# AT89S52_3.net
KiCad netlist of a schematic drawn in Altium Designer
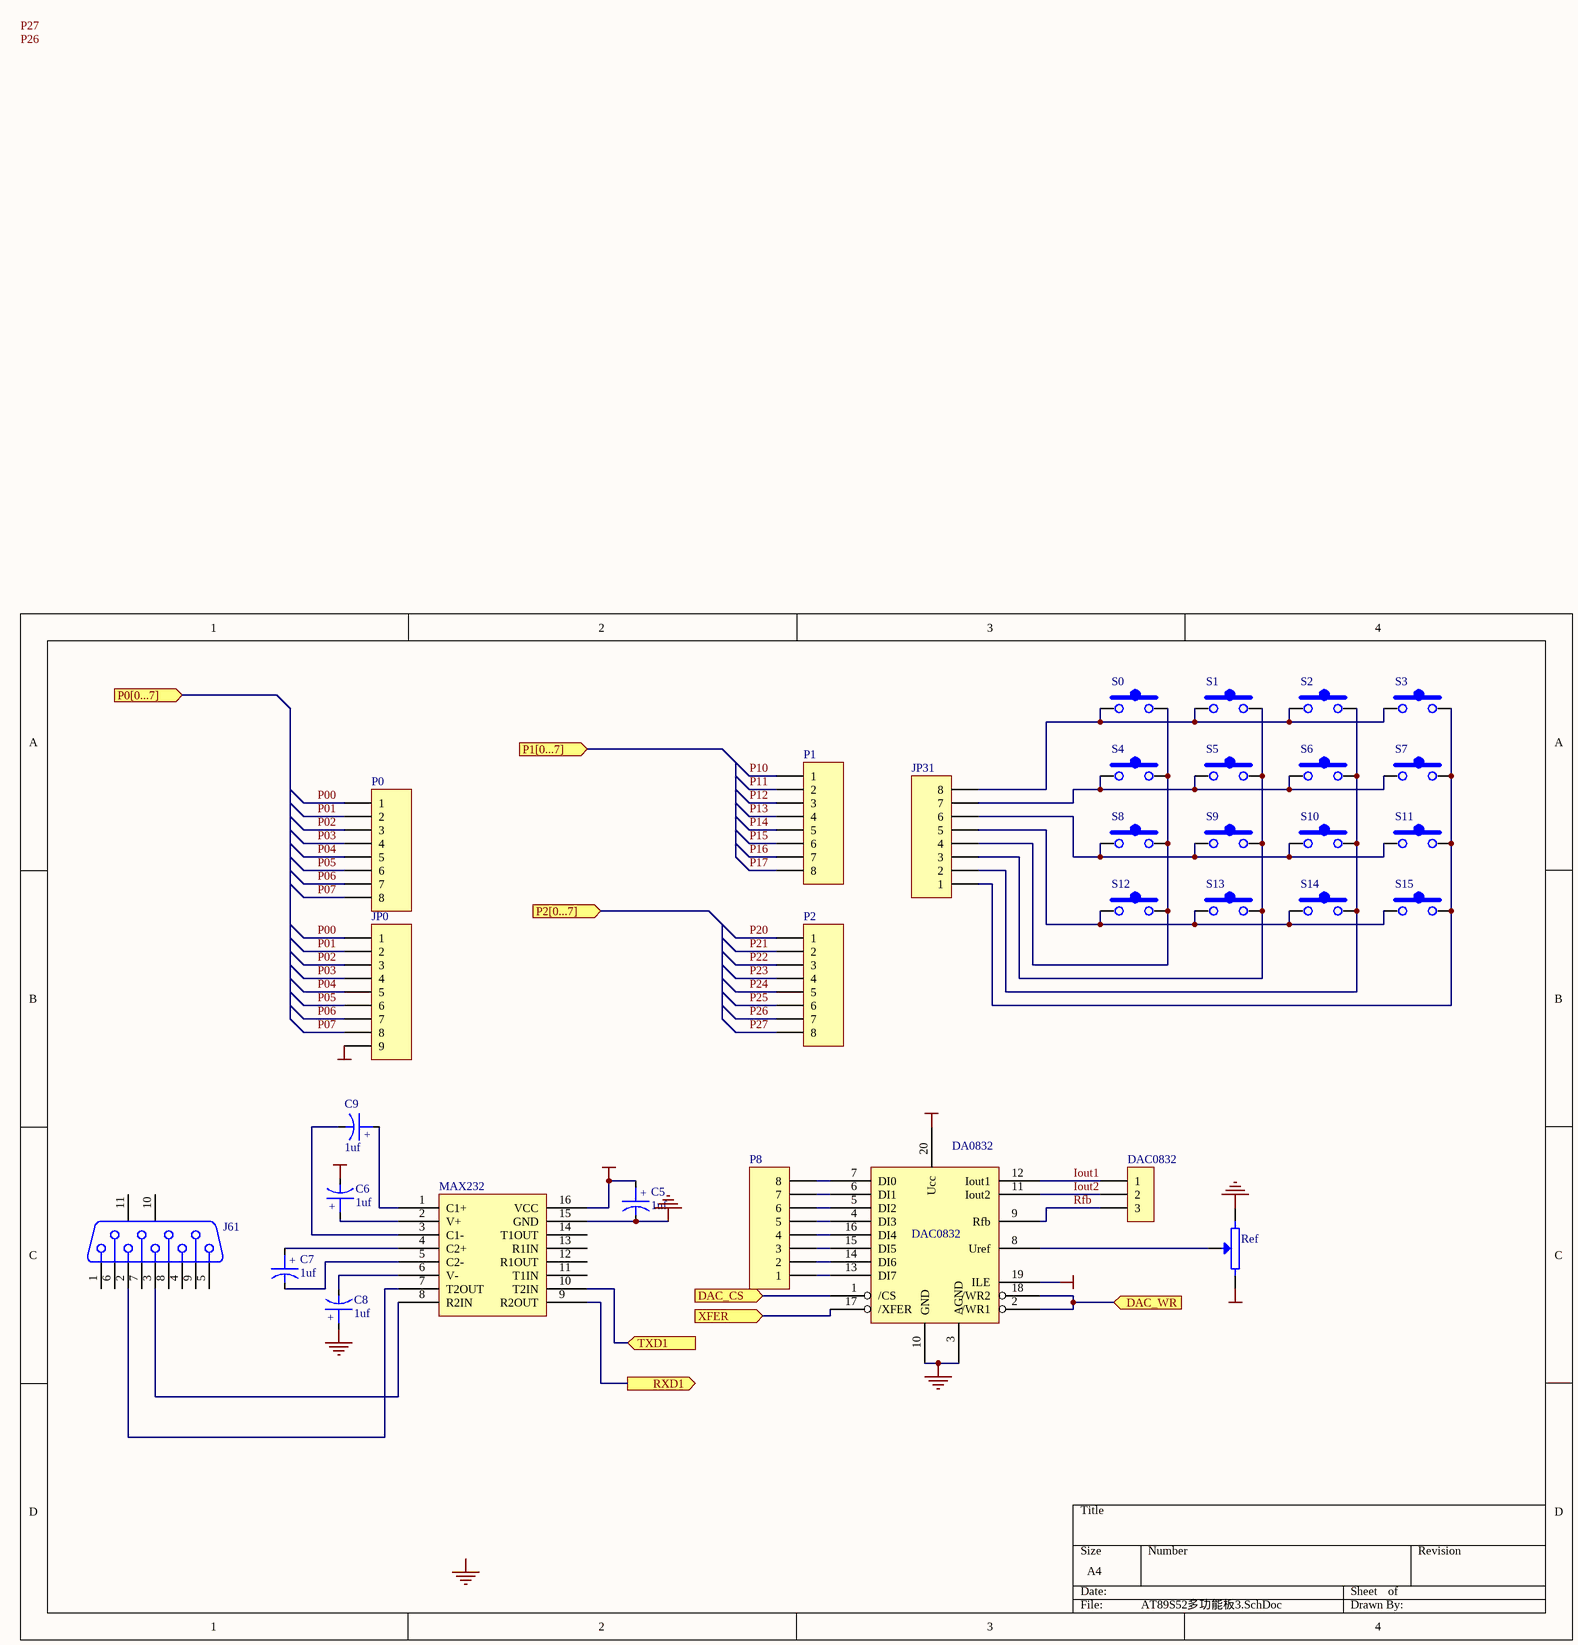
[diagram p0: AT89S52多功能板3.SchDoc]

(export (version "E")
  (design (tool "Eeschema 10.0.6"))
  (components
    (comp (ref "C5")
      (value "1uf")
      (footprint "cap2")
      (description "Capacitor")
      (libsource (lib "*") (part "CAPACITOR POL"))
    )
    (comp (ref "C6")
      (value "1uf")
      (footprint "cap2")
      (description "Capacitor")
      (libsource (lib "*") (part "CAPACITOR POL"))
    )
    (comp (ref "C7")
      (value "1uf")
      (footprint "cap2")
      (description "Capacitor")
      (libsource (lib "*") (part "CAPACITOR POL"))
    )
    (comp (ref "C8")
      (value "1uf")
      (footprint "cap2")
      (description "Capacitor")
      (libsource (lib "*") (part "CAPACITOR POL"))
    )
    (comp (ref "C9")
      (value "1uf")
      (footprint "cap2")
      (description "Capacitor")
      (libsource (lib "*") (part "CAPACITOR POL"))
    )
    (comp (ref "DA0832")
      (value "DA0832")
      (footprint "DAC0832PF")
      (libsource (lib "OldCow1 (1)") (part "DA0832"))
    )
    (comp (ref "DAC0832")
      (value "CON3")
      (footprint "HDR1X3")
      (description "Connector")
      (libsource (lib "OldCow1 (1)") (part "CON3"))
    )
    (comp (ref "J61")
      (value "D Connector 9")
      (footprint "DSUB1.385-2H9")
      (description "Receptacle Assembly, 9 Position, Right Angle")
      (fields (field (name "PUBLISHER") "Altium Limited"))
      (libsource (lib "Miscellaneous Connectors") (part "D Connector 9"))
    )
    (comp (ref "JP0")
      (value "Header 9")
      (footprint "HDR1X9")
      (description "Header, 9-Pin")
      (fields (field (name "PUBLISHER") "Altium Limited"))
      (libsource (lib "Miscellaneous Connectors") (part "Header 9"))
    )
    (comp (ref "JP31")
      (value "Header 8")
      (footprint "HDR1X8")
      (description "Header, 8-Pin")
      (fields (field (name "PUBLISHER") "Altium Limited"))
      (libsource (lib "Miscellaneous Connectors") (part "Header 8"))
    )
    (comp (ref "MAX232") (value "MAX232") (footprint "DIP16") (libsource (lib "*") (part "MAX232")))
    (comp (ref "P0")
      (value "Header 8")
      (footprint "HDR1X8")
      (description "Header, 8-Pin")
      (fields (field (name "PUBLISHER") "Altium Limited"))
      (libsource (lib "") (part "Header 8_1"))
    )
    (comp (ref "P1")
      (value "Header 8")
      (footprint "HDR1X8")
      (description "Header, 8-Pin")
      (fields (field (name "PUBLISHER") "Altium Limited"))
      (libsource (lib "") (part "Header 8_1"))
    )
    (comp (ref "P2")
      (value "Header 8")
      (footprint "HDR1X8")
      (description "Header, 8-Pin")
      (fields (field (name "PUBLISHER") "Altium Limited"))
      (libsource (lib "") (part "Header 8_1"))
    )
    (comp (ref "P8")
      (value "Header 8")
      (footprint "HDR1X8")
      (description "Header, 8-Pin")
      (fields (field (name "PUBLISHER") "Altium Limited"))
      (libsource (lib "Miscellaneous Connectors") (part "Header 8"))
    )
    (comp (ref "Ref")
      (value "25k")
      (footprint "SIP3-D")
      (description "Potentiometer")
      (libsource (lib "OldCow1 (1)") (part "POT2"))
    )
    (comp (ref "S0") (value "KEY") (footprint "KEYPF") (libsource (lib "OldCow1 (1)") (part "KEY")))
    (comp (ref "S1") (value "KEY") (footprint "KEYPF") (libsource (lib "OldCow1 (1)") (part "KEY")))
    (comp (ref "S2") (value "KEY") (footprint "KEYPF") (libsource (lib "OldCow1 (1)") (part "KEY")))
    (comp (ref "S3") (value "KEY") (footprint "KEYPF") (libsource (lib "OldCow1 (1)") (part "KEY")))
    (comp (ref "S4") (value "KEY") (footprint "KEYPF") (libsource (lib "OldCow1 (1)") (part "KEY")))
    (comp (ref "S5") (value "KEY") (footprint "KEYPF") (libsource (lib "OldCow1 (1)") (part "KEY")))
    (comp (ref "S6") (value "KEY") (footprint "KEYPF") (libsource (lib "OldCow1 (1)") (part "KEY")))
    (comp (ref "S7") (value "KEY") (footprint "KEYPF") (libsource (lib "OldCow1 (1)") (part "KEY")))
    (comp (ref "S8") (value "KEY") (footprint "KEYPF") (libsource (lib "OldCow1 (1)") (part "KEY")))
    (comp (ref "S9") (value "KEY") (footprint "KEYPF") (libsource (lib "OldCow1 (1)") (part "KEY")))
    (comp (ref "S10") (value "KEY") (footprint "KEYPF") (libsource (lib "OldCow1 (1)") (part "KEY")))
    (comp (ref "S11") (value "KEY") (footprint "KEYPF") (libsource (lib "OldCow1 (1)") (part "KEY")))
    (comp (ref "S12") (value "KEY") (footprint "KEYPF") (libsource (lib "OldCow1 (1)") (part "KEY")))
    (comp (ref "S13") (value "KEY") (footprint "KEYPF") (libsource (lib "OldCow1 (1)") (part "KEY")))
    (comp (ref "S14") (value "KEY") (footprint "KEYPF") (libsource (lib "OldCow1 (1)") (part "KEY")))
    (comp (ref "S15") (value "KEY") (footprint "KEYPF") (libsource (lib "OldCow1 (1)") (part "KEY")))
  )
  (nets
    (net (code "1") (name "/DAC_CS") (class "Default")
      (node (ref "DA0832") (pin "1") (pinfunction "/CS_1") (pintype "passive"))
    )
    (net (code "2") (name "/DAC_WR") (class "Default")
      (node (ref "DA0832") (pin "18") (pinfunction "/WR2_18") (pintype "passive"))
      (node (ref "DA0832") (pin "2") (pinfunction "/WR1_2") (pintype "passive"))
    )
    (net (code "3") (name "/Iout1") (class "Default")
      (node (ref "DA0832") (pin "12") (pinfunction "Iout1_12") (pintype "passive"))
      (node (ref "DAC0832") (pin "1") (pinfunction "1_1") (pintype "passive"))
    )
    (net (code "4") (name "/Iout2") (class "Default")
      (node (ref "DA0832") (pin "11") (pinfunction "Iout2_11") (pintype "passive"))
      (node (ref "DAC0832") (pin "2") (pinfunction "2_2") (pintype "passive"))
    )
    (net (code "5") (name "/P00") (class "Default")
      (node (ref "JP0") (pin "1") (pinfunction "1_1") (pintype "passive"))
      (node (ref "P0") (pin "1") (pinfunction "1_1") (pintype "passive"))
    )
    (net (code "7") (name "/P01") (class "Default")
      (node (ref "JP0") (pin "2") (pinfunction "2_2") (pintype "passive"))
      (node (ref "P0") (pin "2") (pinfunction "2_2") (pintype "passive"))
    )
    (net (code "9") (name "/P02") (class "Default")
      (node (ref "JP0") (pin "3") (pinfunction "3_3") (pintype "passive"))
      (node (ref "P0") (pin "3") (pinfunction "3_3") (pintype "passive"))
    )
    (net (code "11") (name "/P03") (class "Default")
      (node (ref "JP0") (pin "4") (pinfunction "4_4") (pintype "passive"))
      (node (ref "P0") (pin "4") (pinfunction "4_4") (pintype "passive"))
    )
    (net (code "12") (name "/P04") (class "Default")
      (node (ref "JP0") (pin "5") (pinfunction "5_5") (pintype "passive"))
      (node (ref "P0") (pin "5") (pinfunction "5_5") (pintype "passive"))
    )
    (net (code "13") (name "/P05") (class "Default")
      (node (ref "JP0") (pin "6") (pinfunction "6_6") (pintype "passive"))
      (node (ref "P0") (pin "6") (pinfunction "6_6") (pintype "passive"))
    )
    (net (code "14") (name "/P06") (class "Default")
      (node (ref "JP0") (pin "7") (pinfunction "7_7") (pintype "passive"))
      (node (ref "P0") (pin "7") (pinfunction "7_7") (pintype "passive"))
    )
    (net (code "15") (name "/P07") (class "Default")
      (node (ref "JP0") (pin "8") (pinfunction "8_8") (pintype "passive"))
      (node (ref "P0") (pin "8") (pinfunction "8_8") (pintype "passive"))
    )
    (net (code "16") (name "/P10") (class "Default")
      (node (ref "P1") (pin "1") (pinfunction "1_1") (pintype "passive"))
    )
    (net (code "17") (name "/P11") (class "Default")
      (node (ref "P1") (pin "2") (pinfunction "2_2") (pintype "passive"))
    )
    (net (code "18") (name "/P12") (class "Default")
      (node (ref "P1") (pin "3") (pinfunction "3_3") (pintype "passive"))
    )
    (net (code "19") (name "/P13") (class "Default")
      (node (ref "P1") (pin "4") (pinfunction "4_4") (pintype "passive"))
    )
    (net (code "20") (name "/P14") (class "Default")
      (node (ref "P1") (pin "5") (pinfunction "5_5") (pintype "passive"))
    )
    (net (code "21") (name "/P15") (class "Default")
      (node (ref "P1") (pin "6") (pinfunction "6_6") (pintype "passive"))
    )
    (net (code "22") (name "/P16") (class "Default")
      (node (ref "P1") (pin "7") (pinfunction "7_7") (pintype "passive"))
    )
    (net (code "23") (name "/P17") (class "Default")
      (node (ref "P1") (pin "8") (pinfunction "8_8") (pintype "passive"))
    )
    (net (code "24") (name "/P20") (class "Default")
      (node (ref "P2") (pin "1") (pinfunction "1_1") (pintype "passive"))
    )
    (net (code "25") (name "/P21") (class "Default")
      (node (ref "P2") (pin "2") (pinfunction "2_2") (pintype "passive"))
    )
    (net (code "26") (name "/P22") (class "Default")
      (node (ref "P2") (pin "3") (pinfunction "3_3") (pintype "passive"))
    )
    (net (code "27") (name "/P23") (class "Default")
      (node (ref "P2") (pin "4") (pinfunction "4_4") (pintype "passive"))
    )
    (net (code "28") (name "/P24") (class "Default")
      (node (ref "P2") (pin "5") (pinfunction "5_5") (pintype "passive"))
    )
    (net (code "29") (name "/P25") (class "Default")
      (node (ref "P2") (pin "6") (pinfunction "6_6") (pintype "passive"))
    )
    (net (code "30") (name "/P26") (class "Default")
      (node (ref "P2") (pin "7") (pinfunction "7_7") (pintype "passive"))
    )
    (net (code "31") (name "/P27") (class "Default")
      (node (ref "P2") (pin "8") (pinfunction "8_8") (pintype "passive"))
    )
    (net (code "32") (name "/RXD1") (class "Default")
      (node (ref "MAX232") (pin "9") (pinfunction "R2OUT_9") (pintype "passive"))
    )
    (net (code "33") (name "/Rfb") (class "Default")
      (node (ref "DA0832") (pin "9") (pinfunction "Rfb_9") (pintype "passive"))
      (node (ref "DAC0832") (pin "3") (pinfunction "3_3") (pintype "passive"))
    )
    (net (code "34") (name "/TXD1") (class "Default")
      (node (ref "MAX232") (pin "10") (pinfunction "T2IN_10") (pintype "passive"))
    )
    (net (code "35") (name "/XFER") (class "Default")
      (node (ref "DA0832") (pin "17") (pinfunction "/XFER_17") (pintype "passive"))
    )
    (net (code "36") (name "GND") (class "Default")
      (node (ref "C5") (pin "2") (pinfunction "2_2") (pintype "passive"))
      (node (ref "C8") (pin "1") (pinfunction "1_1") (pintype "passive"))
      (node (ref "DA0832") (pin "10") (pinfunction "GND_10") (pintype "passive"))
      (node (ref "DA0832") (pin "3") (pinfunction "AGND_3") (pintype "passive"))
      (node (ref "MAX232") (pin "15") (pinfunction "GND_15") (pintype "passive"))
      (node (ref "Ref") (pin "2") (pinfunction "2_2") (pintype "passive"))
    )
    (net (code "37") (name "Net-(DA0832-DI0)") (class "Default")
      (node (ref "DA0832") (pin "7") (pinfunction "DI0_7") (pintype "passive"))
      (node (ref "P8") (pin "8") (pinfunction "8_8") (pintype "passive"))
    )
    (net (code "38") (name "Net-(DA0832-DI1)") (class "Default")
      (node (ref "DA0832") (pin "6") (pinfunction "DI1_6") (pintype "passive"))
      (node (ref "P8") (pin "7") (pinfunction "7_7") (pintype "passive"))
    )
    (net (code "39") (name "Net-(DA0832-DI2)") (class "Default")
      (node (ref "DA0832") (pin "5") (pinfunction "DI2_5") (pintype "passive"))
      (node (ref "P8") (pin "6") (pinfunction "6_6") (pintype "passive"))
    )
    (net (code "40") (name "Net-(DA0832-DI3)") (class "Default")
      (node (ref "DA0832") (pin "4") (pinfunction "DI3_4") (pintype "passive"))
      (node (ref "P8") (pin "5") (pinfunction "5_5") (pintype "passive"))
    )
    (net (code "41") (name "Net-(DA0832-DI4)") (class "Default")
      (node (ref "DA0832") (pin "16") (pinfunction "DI4_16") (pintype "passive"))
      (node (ref "P8") (pin "4") (pinfunction "4_4") (pintype "passive"))
    )
    (net (code "42") (name "Net-(DA0832-DI5)") (class "Default")
      (node (ref "DA0832") (pin "15") (pinfunction "DI5_15") (pintype "passive"))
      (node (ref "P8") (pin "3") (pinfunction "3_3") (pintype "passive"))
    )
    (net (code "43") (name "Net-(DA0832-DI6)") (class "Default")
      (node (ref "DA0832") (pin "14") (pinfunction "DI6_14") (pintype "passive"))
      (node (ref "P8") (pin "2") (pinfunction "2_2") (pintype "passive"))
    )
    (net (code "44") (name "Net-(DA0832-DI7)") (class "Default")
      (node (ref "DA0832") (pin "13") (pinfunction "DI7_13") (pintype "passive"))
      (node (ref "P8") (pin "1") (pinfunction "1_1") (pintype "passive"))
    )
    (net (code "45") (name "Net-(DA0832-Uref)") (class "Default")
      (node (ref "DA0832") (pin "8") (pinfunction "Uref_8") (pintype "passive"))
      (node (ref "Ref") (pin "3") (pinfunction "W_3") (pintype "passive"))
    )
    (net (code "46") (name "Net-(JP31-Pad1)") (class "Default")
      (node (ref "JP31") (pin "1") (pinfunction "1_1") (pintype "passive"))
      (node (ref "S11") (pin "2") (pinfunction "2_2") (pintype "passive"))
      (node (ref "S15") (pin "2") (pinfunction "2_2") (pintype "passive"))
      (node (ref "S3") (pin "2") (pinfunction "2_2") (pintype "passive"))
      (node (ref "S7") (pin "2") (pinfunction "2_2") (pintype "passive"))
    )
    (net (code "47") (name "Net-(JP31-Pad2)") (class "Default")
      (node (ref "JP31") (pin "2") (pinfunction "2_2") (pintype "passive"))
      (node (ref "S10") (pin "2") (pinfunction "2_2") (pintype "passive"))
      (node (ref "S14") (pin "2") (pinfunction "2_2") (pintype "passive"))
      (node (ref "S2") (pin "2") (pinfunction "2_2") (pintype "passive"))
      (node (ref "S6") (pin "2") (pinfunction "2_2") (pintype "passive"))
    )
    (net (code "48") (name "Net-(JP31-Pad3)") (class "Default")
      (node (ref "JP31") (pin "3") (pinfunction "3_3") (pintype "passive"))
      (node (ref "S1") (pin "2") (pinfunction "2_2") (pintype "passive"))
      (node (ref "S13") (pin "2") (pinfunction "2_2") (pintype "passive"))
      (node (ref "S5") (pin "2") (pinfunction "2_2") (pintype "passive"))
      (node (ref "S9") (pin "2") (pinfunction "2_2") (pintype "passive"))
    )
    (net (code "49") (name "Net-(JP31-Pad4)") (class "Default")
      (node (ref "JP31") (pin "4") (pinfunction "4_4") (pintype "passive"))
      (node (ref "S0") (pin "2") (pinfunction "2_2") (pintype "passive"))
      (node (ref "S12") (pin "2") (pinfunction "2_2") (pintype "passive"))
      (node (ref "S4") (pin "2") (pinfunction "2_2") (pintype "passive"))
      (node (ref "S8") (pin "2") (pinfunction "2_2") (pintype "passive"))
    )
    (net (code "50") (name "Net-(JP31-Pad5)") (class "Default")
      (node (ref "JP31") (pin "5") (pinfunction "5_5") (pintype "passive"))
      (node (ref "S12") (pin "1") (pinfunction "1_1") (pintype "passive"))
      (node (ref "S13") (pin "1") (pinfunction "1_1") (pintype "passive"))
      (node (ref "S14") (pin "1") (pinfunction "1_1") (pintype "passive"))
      (node (ref "S15") (pin "1") (pinfunction "1_1") (pintype "passive"))
    )
    (net (code "51") (name "Net-(JP31-Pad6)") (class "Default")
      (node (ref "JP31") (pin "6") (pinfunction "6_6") (pintype "passive"))
      (node (ref "S10") (pin "1") (pinfunction "1_1") (pintype "passive"))
      (node (ref "S11") (pin "1") (pinfunction "1_1") (pintype "passive"))
      (node (ref "S8") (pin "1") (pinfunction "1_1") (pintype "passive"))
      (node (ref "S9") (pin "1") (pinfunction "1_1") (pintype "passive"))
    )
    (net (code "52") (name "Net-(JP31-Pad7)") (class "Default")
      (node (ref "JP31") (pin "7") (pinfunction "7_7") (pintype "passive"))
      (node (ref "S4") (pin "1") (pinfunction "1_1") (pintype "passive"))
      (node (ref "S5") (pin "1") (pinfunction "1_1") (pintype "passive"))
      (node (ref "S6") (pin "1") (pinfunction "1_1") (pintype "passive"))
      (node (ref "S7") (pin "1") (pinfunction "1_1") (pintype "passive"))
    )
    (net (code "53") (name "Net-(JP31-Pad8)") (class "Default")
      (node (ref "JP31") (pin "8") (pinfunction "8_8") (pintype "passive"))
      (node (ref "S0") (pin "1") (pinfunction "1_1") (pintype "passive"))
      (node (ref "S1") (pin "1") (pinfunction "1_1") (pintype "passive"))
      (node (ref "S2") (pin "1") (pinfunction "1_1") (pintype "passive"))
      (node (ref "S3") (pin "1") (pinfunction "1_1") (pintype "passive"))
    )
    (net (code "54") (name "Net-(MAX232-C1+)") (class "Default")
      (node (ref "C9") (pin "1") (pinfunction "1_1") (pintype "passive"))
      (node (ref "MAX232") (pin "1") (pinfunction "C1+_1") (pintype "passive"))
    )
    (net (code "55") (name "Net-(MAX232-C1-)") (class "Default")
      (node (ref "C9") (pin "2") (pinfunction "2_2") (pintype "passive"))
      (node (ref "MAX232") (pin "3") (pinfunction "C1-_3") (pintype "passive"))
    )
    (net (code "56") (name "Net-(MAX232-C2+)") (class "Default")
      (node (ref "C7") (pin "1") (pinfunction "1_1") (pintype "passive"))
      (node (ref "MAX232") (pin "4") (pinfunction "C2+_4") (pintype "passive"))
    )
    (net (code "57") (name "Net-(MAX232-C2-)") (class "Default")
      (node (ref "C7") (pin "2") (pinfunction "2_2") (pintype "passive"))
      (node (ref "MAX232") (pin "5") (pinfunction "C2-_5") (pintype "passive"))
    )
    (net (code "58") (name "Net-(MAX232-R2IN)") (class "Default")
      (node (ref "J61") (pin "3") (pinfunction "3_3") (pintype "passive"))
      (node (ref "MAX232") (pin "8") (pinfunction "R2IN_8") (pintype "passive"))
    )
    (net (code "59") (name "Net-(MAX232-T2OUT)") (class "Default")
      (node (ref "J61") (pin "2") (pinfunction "2_2") (pintype "passive"))
      (node (ref "MAX232") (pin "7") (pinfunction "T2OUT_7") (pintype "passive"))
    )
    (net (code "60") (name "Net-(MAX232-V+)") (class "Default")
      (node (ref "C6") (pin "1") (pinfunction "1_1") (pintype "passive"))
      (node (ref "MAX232") (pin "2") (pinfunction "V+_2") (pintype "passive"))
    )
    (net (code "61") (name "Net-(MAX232-V-)") (class "Default")
      (node (ref "C8") (pin "2") (pinfunction "2_2") (pintype "passive"))
      (node (ref "MAX232") (pin "6") (pinfunction "V-_6") (pintype "passive"))
    )
    (net (code "62") (name "VCC") (class "Default")
      (node (ref "C5") (pin "1") (pinfunction "1_1") (pintype "passive"))
      (node (ref "C6") (pin "2") (pinfunction "2_2") (pintype "passive"))
      (node (ref "DA0832") (pin "19") (pinfunction "ILE_19") (pintype "passive"))
      (node (ref "DA0832") (pin "20") (pinfunction "Ucc_20") (pintype "passive"))
      (node (ref "JP0") (pin "9") (pinfunction "9_9") (pintype "passive"))
      (node (ref "MAX232") (pin "16") (pinfunction "VCC_16") (pintype "passive"))
      (node (ref "Ref") (pin "1") (pinfunction "1_1") (pintype "passive"))
    )
    (net (code "63") (name "unconnected-(J61-MH1-Pad10)") (class "Default")
      (node (ref "J61") (pin "10") (pinfunction "MH1_10") (pintype "passive"))
    )
    (net (code "64") (name "unconnected-(J61-MH2-Pad11)") (class "Default")
      (node (ref "J61") (pin "11") (pinfunction "MH2_11") (pintype "passive"))
    )
    (net (code "65") (name "unconnected-(J61-Pad1)") (class "Default")
      (node (ref "J61") (pin "1") (pinfunction "1_1") (pintype "passive"))
    )
    (net (code "66") (name "unconnected-(J61-Pad4)") (class "Default")
      (node (ref "J61") (pin "4") (pinfunction "4_4") (pintype "passive"))
    )
    (net (code "67") (name "unconnected-(J61-Pad5)") (class "Default")
      (node (ref "J61") (pin "5") (pinfunction "5_5") (pintype "passive"))
    )
    (net (code "68") (name "unconnected-(J61-Pad6)") (class "Default")
      (node (ref "J61") (pin "6") (pinfunction "6_6") (pintype "passive"))
    )
    (net (code "69") (name "unconnected-(J61-Pad7)") (class "Default")
      (node (ref "J61") (pin "7") (pinfunction "7_7") (pintype "passive"))
    )
    (net (code "70") (name "unconnected-(J61-Pad8)") (class "Default")
      (node (ref "J61") (pin "8") (pinfunction "8_8") (pintype "passive"))
    )
    (net (code "71") (name "unconnected-(J61-Pad9)") (class "Default")
      (node (ref "J61") (pin "9") (pinfunction "9_9") (pintype "passive"))
    )
    (net (code "72") (name "unconnected-(MAX232-R1IN-Pad13)") (class "Default")
      (node (ref "MAX232") (pin "13") (pinfunction "R1IN_13") (pintype "passive"))
    )
    (net (code "73") (name "unconnected-(MAX232-R1OUT-Pad12)") (class "Default")
      (node (ref "MAX232") (pin "12") (pinfunction "R1OUT_12") (pintype "passive"))
    )
    (net (code "74") (name "unconnected-(MAX232-T1IN-Pad11)") (class "Default")
      (node (ref "MAX232") (pin "11") (pinfunction "T1IN_11") (pintype "passive"))
    )
    (net (code "75") (name "unconnected-(MAX232-T1OUT-Pad14)") (class "Default")
      (node (ref "MAX232") (pin "14") (pinfunction "T1OUT_14") (pintype "passive"))
    )
  )
)
